# FANCTRL.net
KiCad netlist of a schematic drawn in EAGLE
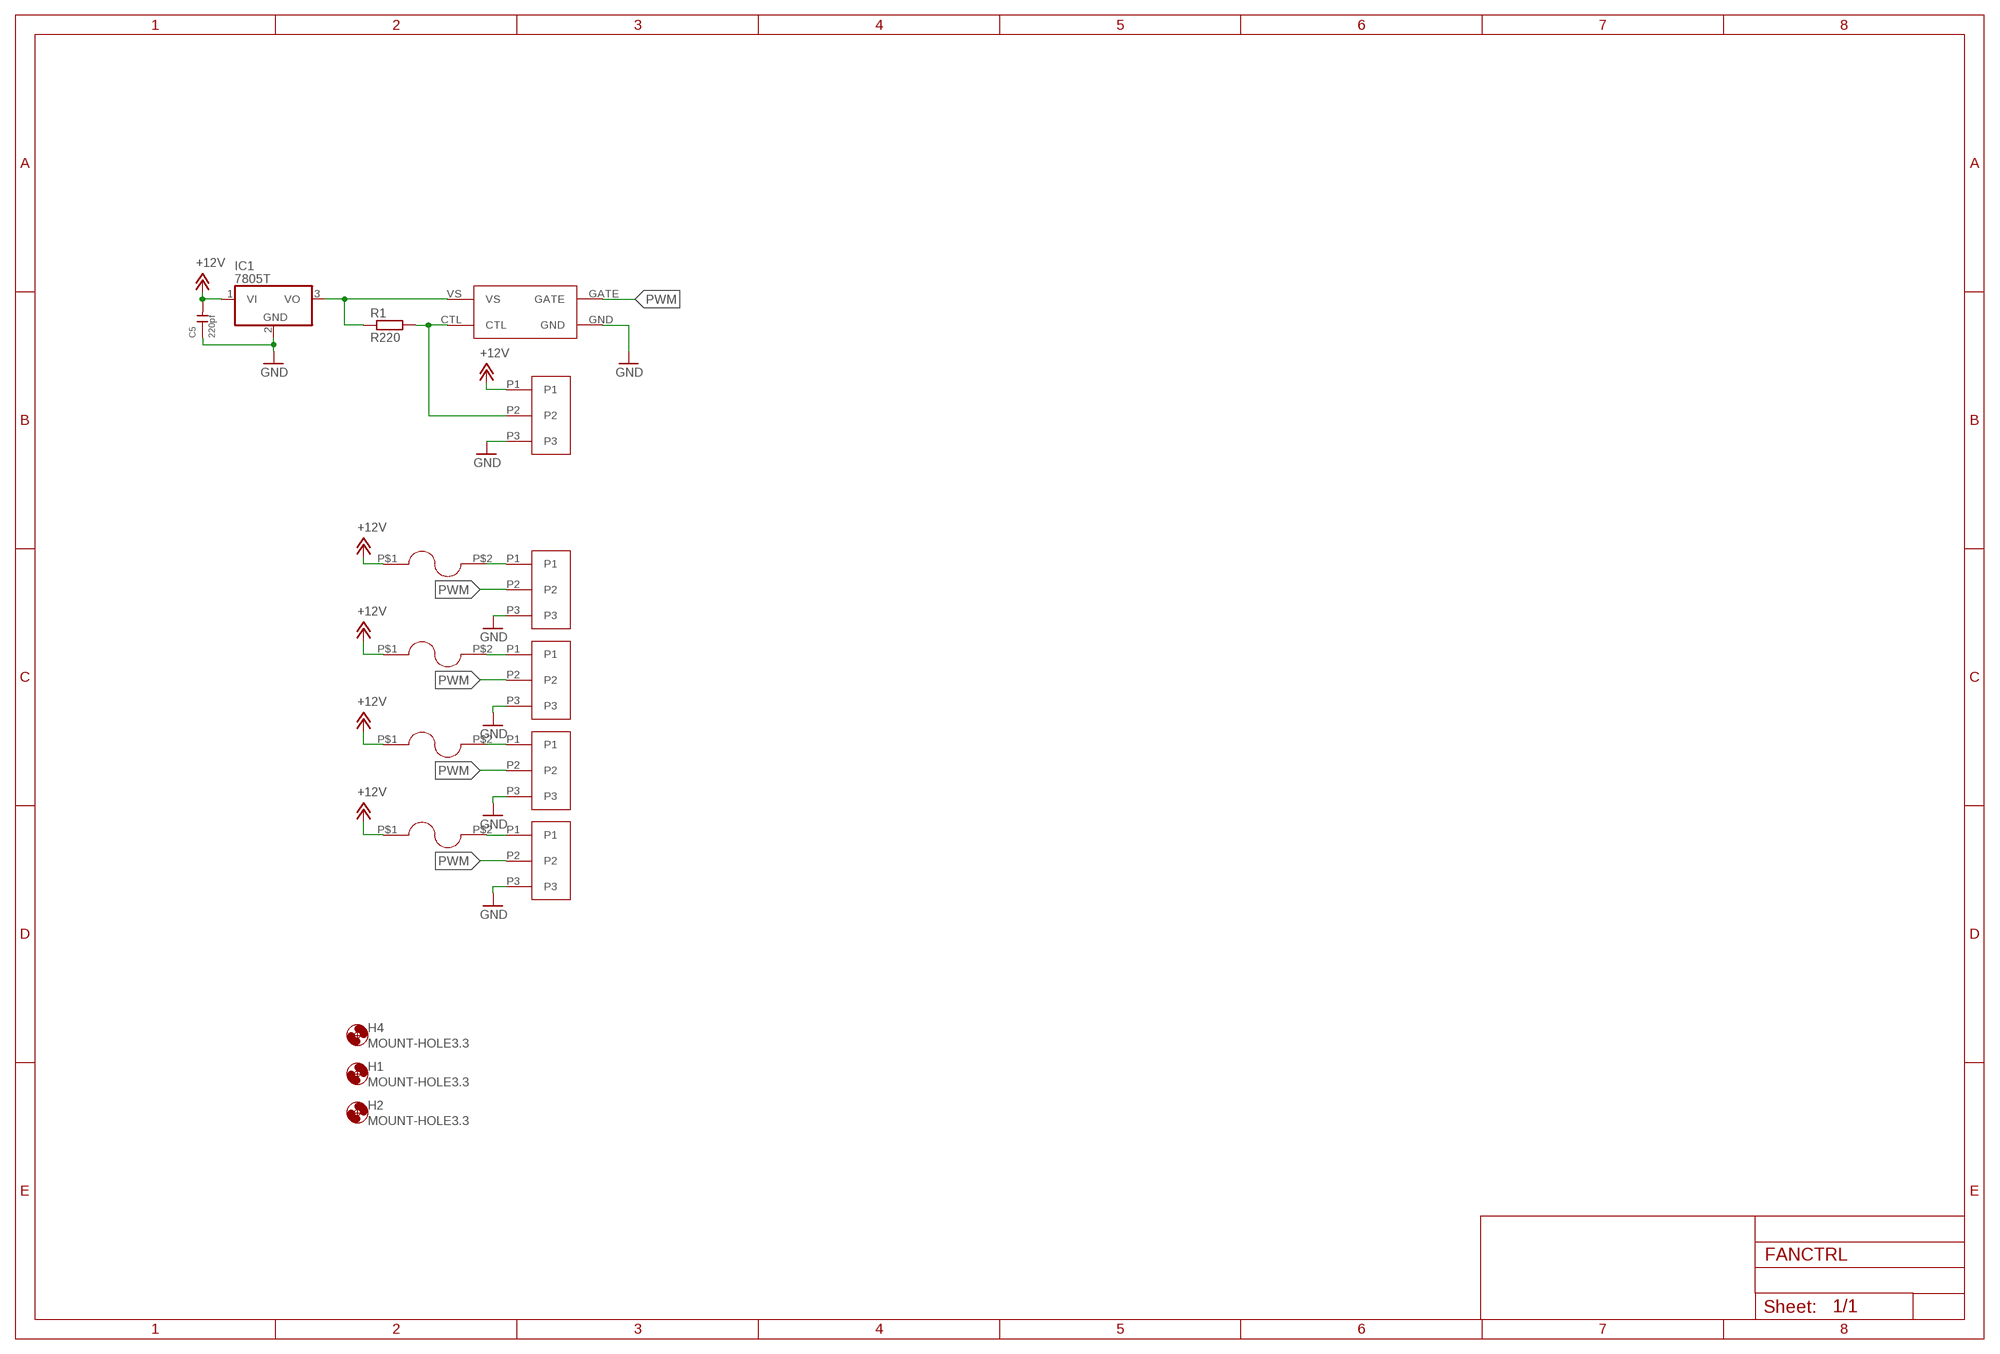
[diagram p0: schematic, sheet 1]

(export (version "E")
  (design (tool "Eeschema 10.0.6"))
  (components
    (comp (ref "C5")
      (value "220pf")
      (footprint "eagle-import:C0402")
      (fields (field (name "MPN") "CC0402JRNPO9BN221"))
      (libsource (lib "eagle-import") (part "CERAMIC-220PF-50V-5%-NPO(0402)"))
    )
    (comp (ref "H1")
      (value "MOUNT-HOLE3.3")
      (footprint "eagle-import:3,3")
      (libsource (lib "eagle-import") (part "MOUNT-HOLE3.3"))
    )
    (comp (ref "H2")
      (value "MOUNT-HOLE3.3")
      (footprint "eagle-import:3,3")
      (libsource (lib "eagle-import") (part "MOUNT-HOLE3.3"))
    )
    (comp (ref "H4")
      (value "MOUNT-HOLE3.3")
      (footprint "eagle-import:3,3")
      (libsource (lib "eagle-import") (part "MOUNT-HOLE3.3"))
    )
    (comp (ref "IC1")
      (value "7805T")
      (footprint "eagle-import:TO220H")
      (libsource (lib "eagle-import") (part "78T05"))
    )
    (comp (ref "R1")
      (value "R220")
      (footprint "eagle-import:R0805")
      (libsource (lib "eagle-import") (part "R-EU_R0805"))
    )
    (comp (ref "U$1")
      (value "1935789")
      (footprint "eagle-import:1935789")
      (libsource (lib "eagle-import") (part "1935789"))
    )
    (comp (ref "U$2")
      (value "1935789")
      (footprint "eagle-import:1935789")
      (libsource (lib "eagle-import") (part "1935789"))
    )
    (comp (ref "U$3")
      (value "1935789")
      (footprint "eagle-import:1935789")
      (libsource (lib "eagle-import") (part "1935789"))
    )
    (comp (ref "U$4")
      (value "1935789")
      (footprint "eagle-import:1935789")
      (libsource (lib "eagle-import") (part "1935789"))
    )
    (comp (ref "U$5")
      (value "2920L400/15MR")
      (footprint "eagle-import:2920L400_15MR")
      (libsource (lib "eagle-import") (part "2920L400/15MR"))
    )
    (comp (ref "U$6")
      (value "2920L400/15MR")
      (footprint "eagle-import:2920L400_15MR")
      (libsource (lib "eagle-import") (part "2920L400/15MR"))
    )
    (comp (ref "U$7")
      (value "2920L400/15MR")
      (footprint "eagle-import:2920L400_15MR")
      (libsource (lib "eagle-import") (part "2920L400/15MR"))
    )
    (comp (ref "U$8")
      (value "2920L400/15MR")
      (footprint "eagle-import:2920L400_15MR")
      (libsource (lib "eagle-import") (part "2920L400/15MR"))
    )
    (comp (ref "U$9")
      (value "1935789")
      (footprint "eagle-import:1935789")
      (libsource (lib "eagle-import") (part "1935789"))
    )
    (comp (ref "U$15")
      (value "MIC4417")
      (footprint "eagle-import:PDM_2019_REVB_MIC4416YM4-TR")
      (libsource (lib "eagle-import") (part "MIC4417"))
    )
  )
  (nets
    (net (code "1") (name "+12V") (class "Default")
      (node (ref "C5") (pin "2") (pinfunction "2_2") (pintype "passive"))
      (node (ref "IC1") (pin "1") (pinfunction "VI_1") (pintype "input"))
      (node (ref "U$1") (pin "P1") (pinfunction "P1_P1") (pintype "bidirectional"))
      (node (ref "U$5") (pin "P$1") (pinfunction "P$1_P$1") (pintype "bidirectional"))
      (node (ref "U$6") (pin "P$1") (pinfunction "P$1_P$1") (pintype "bidirectional"))
      (node (ref "U$7") (pin "P$1") (pinfunction "P$1_P$1") (pintype "bidirectional"))
      (node (ref "U$8") (pin "P$1") (pinfunction "P$1_P$1") (pintype "bidirectional"))
    )
    (net (code "2") (name "GND") (class "Default")
      (node (ref "C5") (pin "1") (pinfunction "1_1") (pintype "passive"))
      (node (ref "IC1") (pin "2") (pinfunction "GND_2") (pintype "passive"))
      (node (ref "U$1") (pin "P3") (pinfunction "P3_P3") (pintype "bidirectional"))
      (node (ref "U$15") (pin "GND") (pinfunction "GND_GND") (pintype "bidirectional"))
      (node (ref "U$2") (pin "P3") (pinfunction "P3_P3") (pintype "bidirectional"))
      (node (ref "U$3") (pin "P3") (pinfunction "P3_P3") (pintype "bidirectional"))
      (node (ref "U$4") (pin "P3") (pinfunction "P3_P3") (pintype "bidirectional"))
      (node (ref "U$9") (pin "P3") (pinfunction "P3_P3") (pintype "bidirectional"))
    )
    (net (code "3") (name "Net-(IC1-VO)") (class "Default")
      (node (ref "IC1") (pin "3") (pinfunction "VO_3") (pintype "passive"))
      (node (ref "R1") (pin "1") (pinfunction "1_1") (pintype "passive"))
      (node (ref "U$15") (pin "VS") (pinfunction "VS_VS") (pintype "bidirectional"))
    )
    (net (code "4") (name "Net-(R1-Pad2)") (class "Default")
      (node (ref "R1") (pin "2") (pinfunction "2_2") (pintype "passive"))
      (node (ref "U$1") (pin "P2") (pinfunction "P2_P2") (pintype "bidirectional"))
      (node (ref "U$15") (pin "CTL") (pinfunction "CTL_CTL") (pintype "bidirectional"))
    )
    (net (code "5") (name "Net-(U$2-PadP1)") (class "Default")
      (node (ref "U$2") (pin "P1") (pinfunction "P1_P1") (pintype "bidirectional"))
      (node (ref "U$5") (pin "P$2") (pinfunction "P$2_P$2") (pintype "bidirectional"))
    )
    (net (code "6") (name "Net-(U$3-PadP1)") (class "Default")
      (node (ref "U$3") (pin "P1") (pinfunction "P1_P1") (pintype "bidirectional"))
      (node (ref "U$6") (pin "P$2") (pinfunction "P$2_P$2") (pintype "bidirectional"))
    )
    (net (code "7") (name "Net-(U$4-PadP1)") (class "Default")
      (node (ref "U$4") (pin "P1") (pinfunction "P1_P1") (pintype "bidirectional"))
      (node (ref "U$7") (pin "P$2") (pinfunction "P$2_P$2") (pintype "bidirectional"))
    )
    (net (code "8") (name "Net-(U$8-PadP$2)") (class "Default")
      (node (ref "U$8") (pin "P$2") (pinfunction "P$2_P$2") (pintype "bidirectional"))
      (node (ref "U$9") (pin "P1") (pinfunction "P1_P1") (pintype "bidirectional"))
    )
    (net (code "9") (name "PWM") (class "Default")
      (node (ref "U$15") (pin "GATE") (pinfunction "GATE_GATE") (pintype "bidirectional"))
      (node (ref "U$2") (pin "P2") (pinfunction "P2_P2") (pintype "bidirectional"))
      (node (ref "U$3") (pin "P2") (pinfunction "P2_P2") (pintype "bidirectional"))
      (node (ref "U$4") (pin "P2") (pinfunction "P2_P2") (pintype "bidirectional"))
      (node (ref "U$9") (pin "P2") (pinfunction "P2_P2") (pintype "bidirectional"))
    )
  )
)
